# analog-out.net
KiCad netlist of a schematic drawn in EAGLE
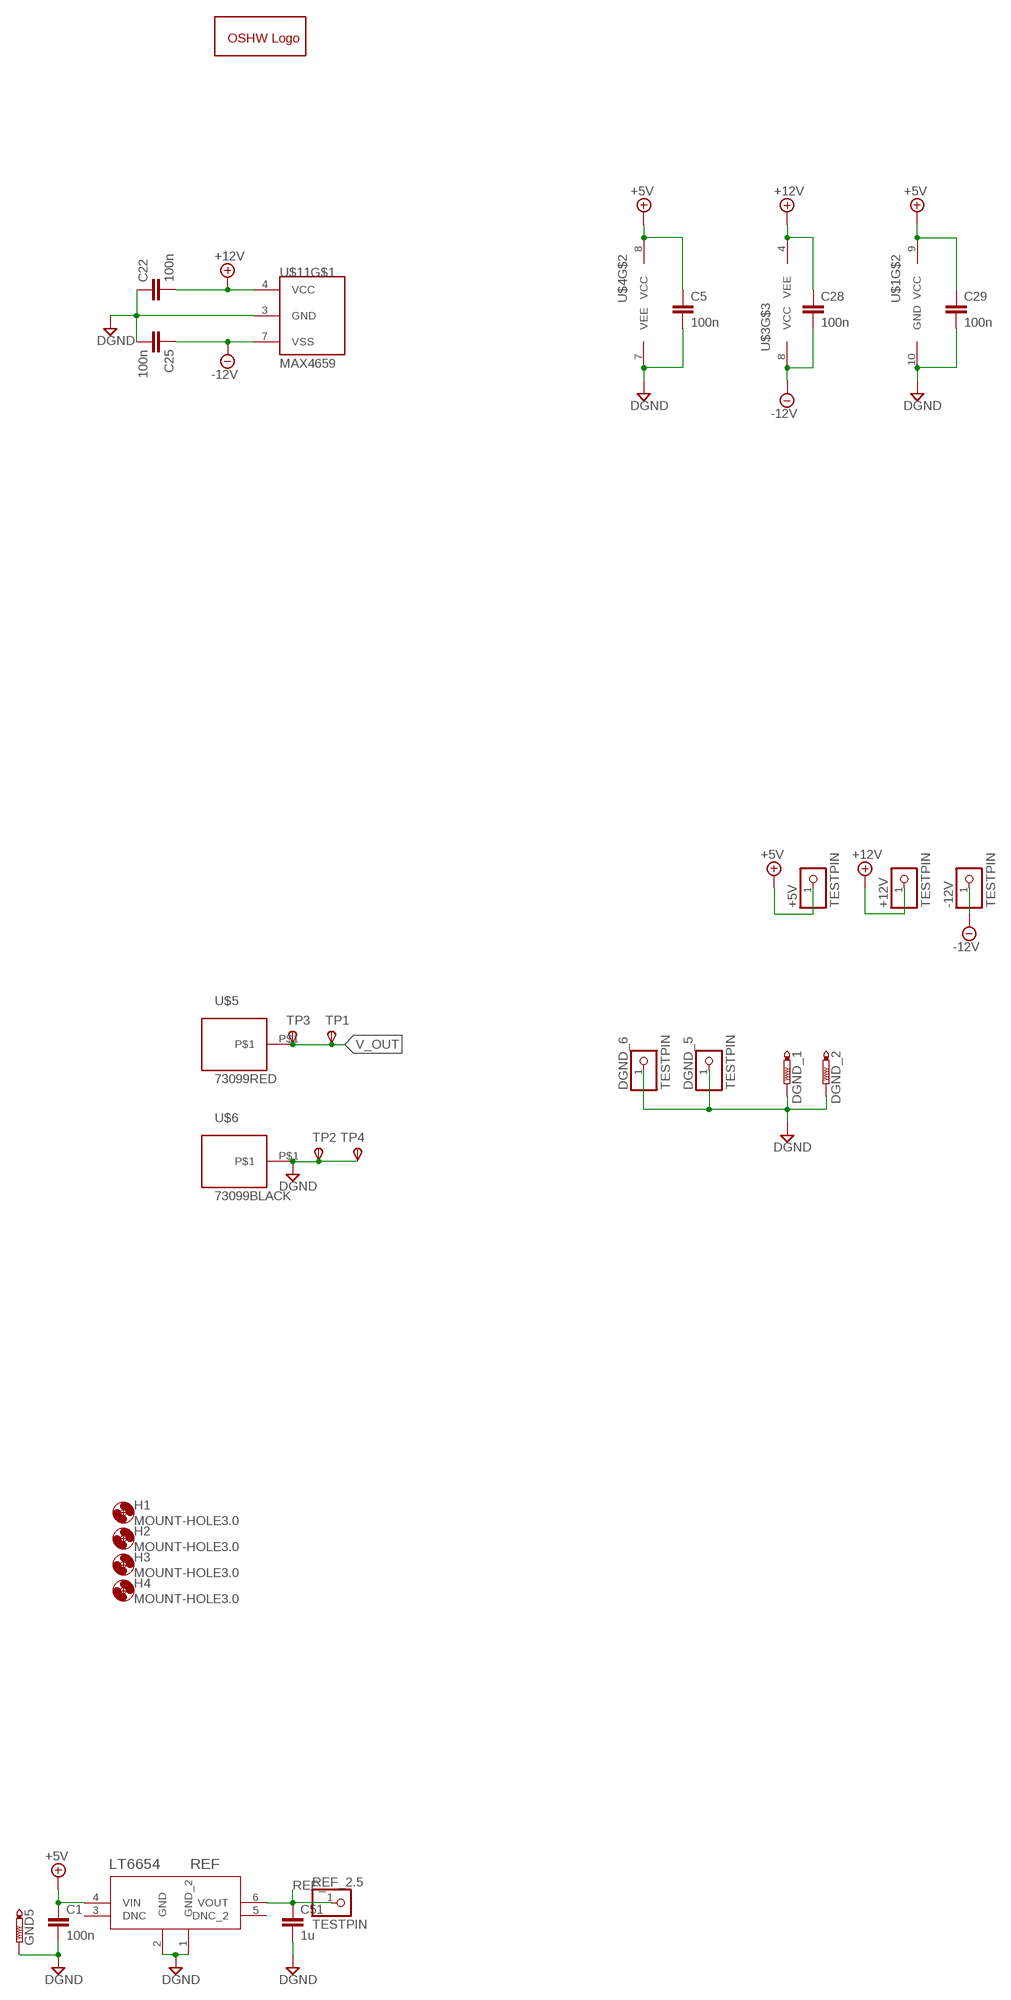
[diagram p0: schematic, sheet 1, part 1 of 2]
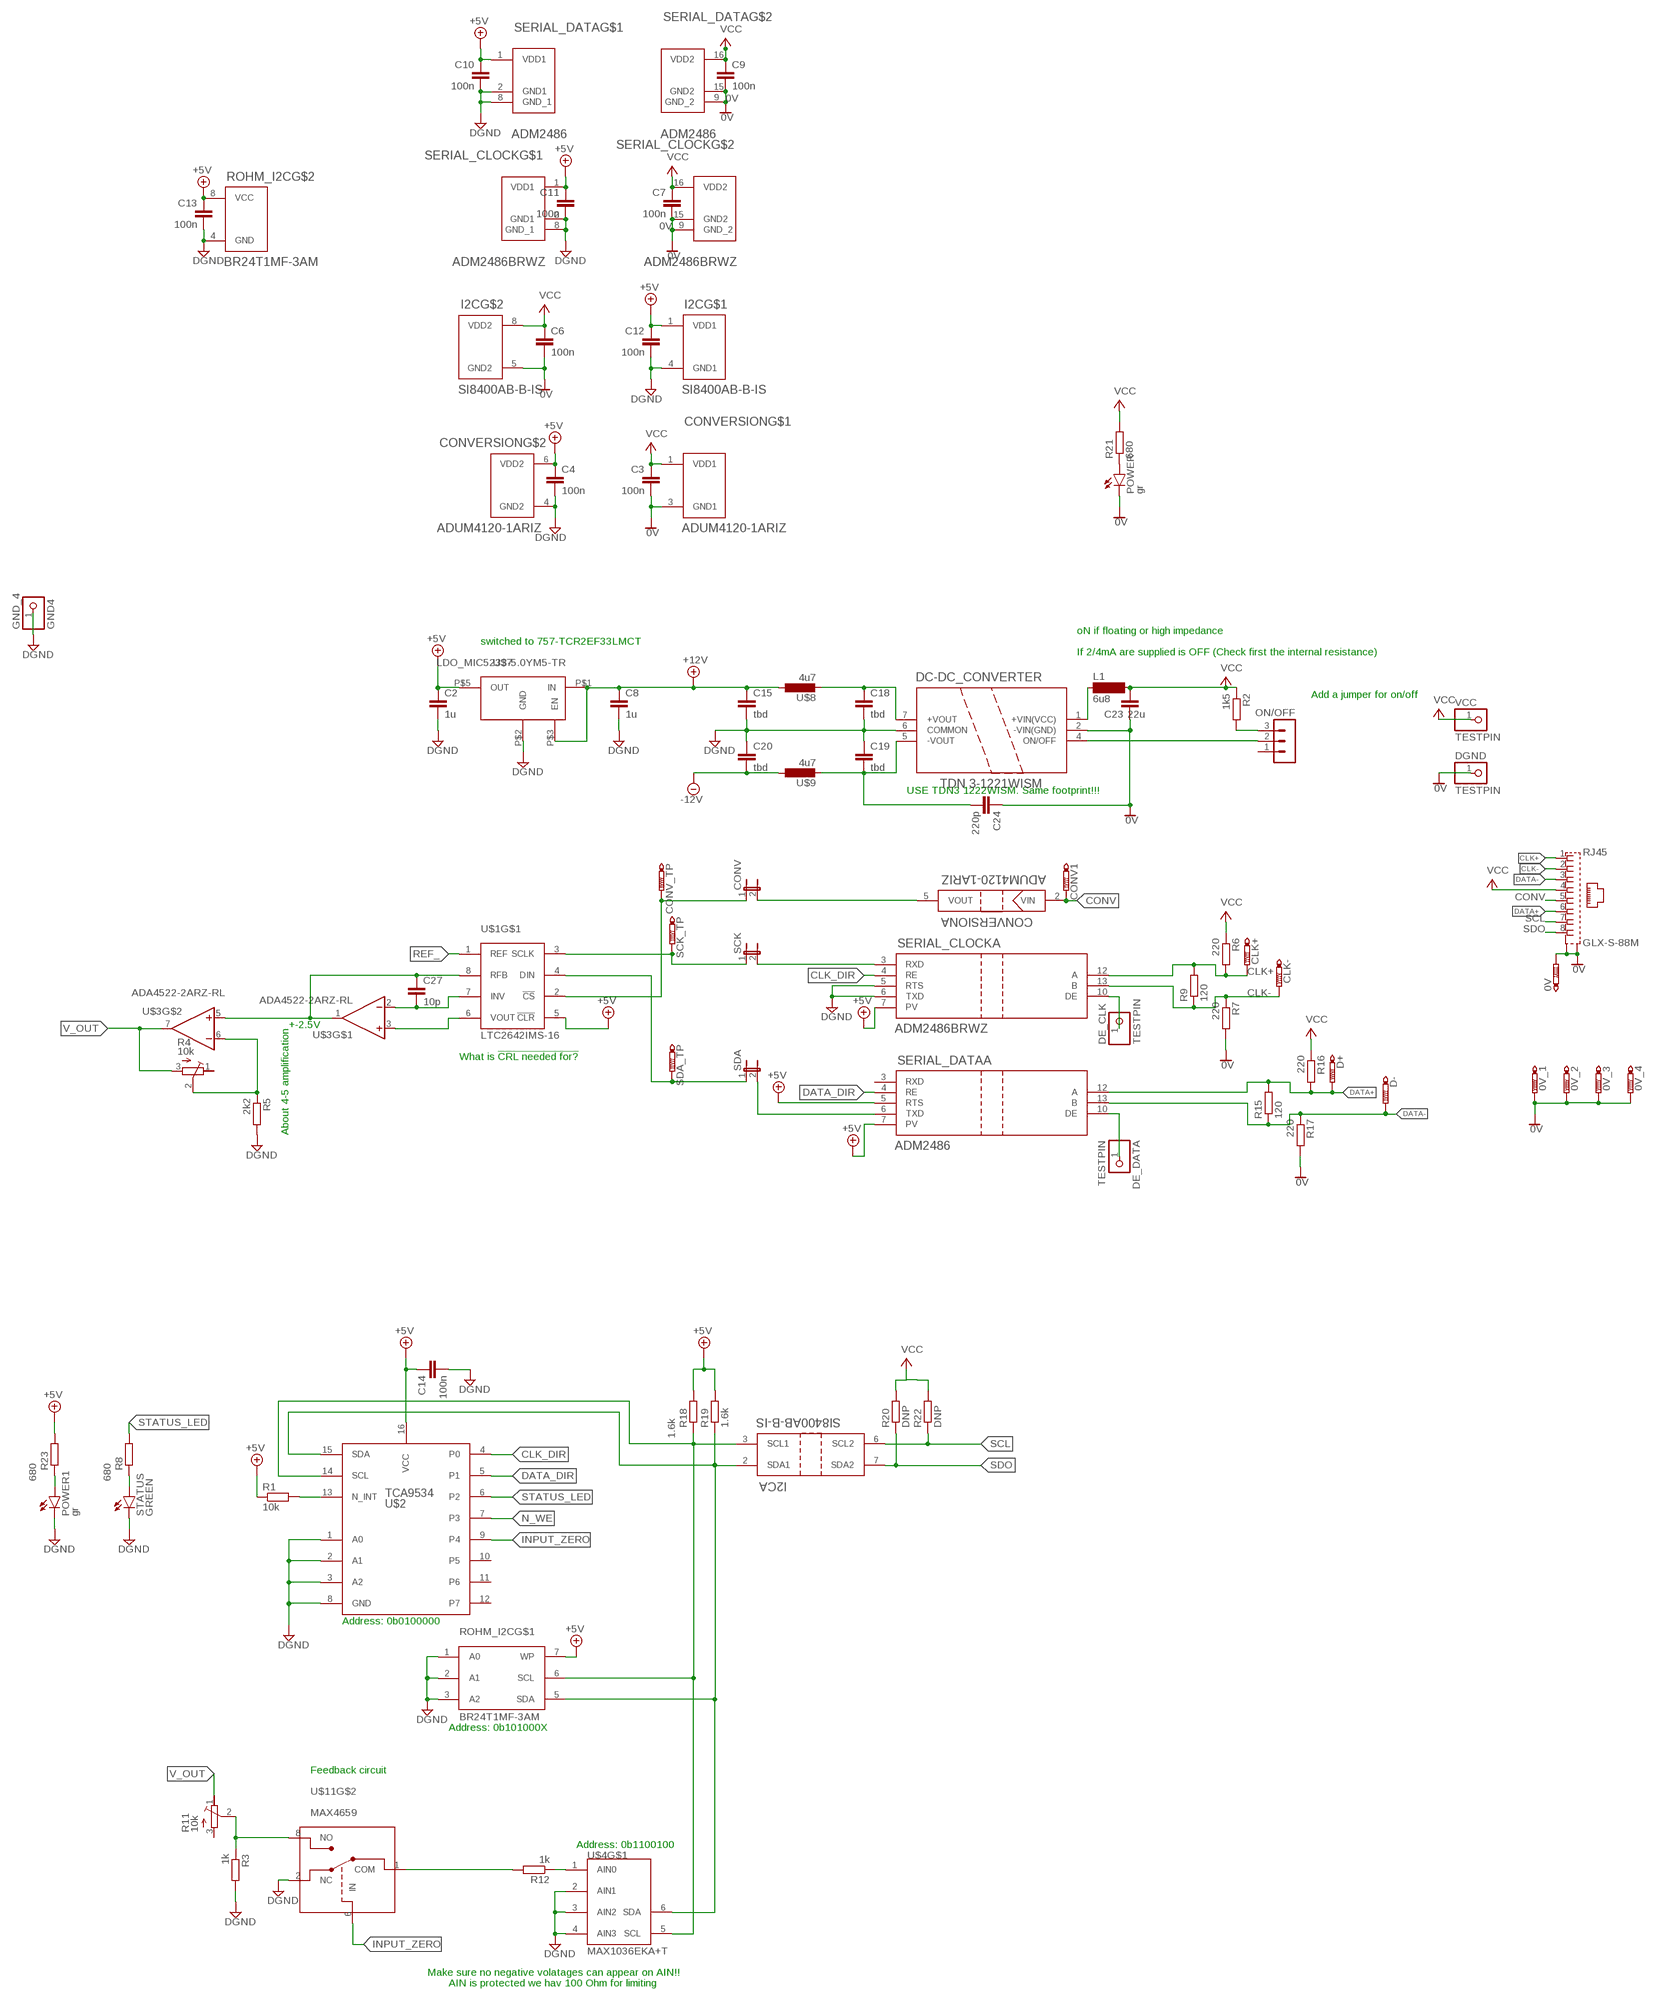
[diagram p1: schematic, sheet 1, part 2 of 2]

(export (version "E")
  (design (tool "Eeschema 10.0.6"))
  (components
    (comp (ref "+5V")
      (value "TESTPIN")
      (footprint "eagle-import:1X01")
      (libsource (lib "eagle-import") (part "TESTPIN"))
    )
    (comp (ref "+12V")
      (value "TESTPIN")
      (footprint "eagle-import:1X01")
      (libsource (lib "eagle-import") (part "TESTPIN"))
    )
    (comp (ref "-12V")
      (value "TESTPIN")
      (footprint "eagle-import:1X01")
      (libsource (lib "eagle-import") (part "TESTPIN"))
    )
    (comp (ref "0V")
      (value "PTR1B1,27")
      (footprint "eagle-import:B1,27")
      (libsource (lib "eagle-import") (part "PTR1B1,27"))
    )
    (comp (ref "0V_1")
      (value "PTR1B1,27")
      (footprint "eagle-import:B1,27")
      (libsource (lib "eagle-import") (part "PTR1B1,27"))
    )
    (comp (ref "0V_2")
      (value "PTR1B1,27")
      (footprint "eagle-import:B1,27")
      (libsource (lib "eagle-import") (part "PTR1B1,27"))
    )
    (comp (ref "0V_3")
      (value "PTR1B1,27")
      (footprint "eagle-import:B1,27")
      (libsource (lib "eagle-import") (part "PTR1B1,27"))
    )
    (comp (ref "0V_4")
      (value "PTR1B1,27")
      (footprint "eagle-import:B1,27")
      (libsource (lib "eagle-import") (part "PTR1B1,27"))
    )
    (comp (ref "C1")
      (value "100n")
      (footprint "eagle-import:C0805")
      (libsource (lib "eagle-import") (part "C-EUC0805"))
    )
    (comp (ref "C2")
      (value "1u")
      (footprint "eagle-import:C0805K")
      (libsource (lib "eagle-import") (part "C-EUC0805K"))
    )
    (comp (ref "C3")
      (value "100n")
      (footprint "eagle-import:C0805K")
      (libsource (lib "eagle-import") (part "C-EUC0805K"))
    )
    (comp (ref "C4")
      (value "100n")
      (footprint "eagle-import:C0805K")
      (libsource (lib "eagle-import") (part "C-EUC0805K"))
    )
    (comp (ref "C5")
      (value "100n")
      (footprint "eagle-import:C0805")
      (libsource (lib "eagle-import") (part "C-EUC0805"))
    )
    (comp (ref "C6")
      (value "100n")
      (footprint "eagle-import:C0805K")
      (libsource (lib "eagle-import") (part "C-EUC0805K"))
    )
    (comp (ref "C7")
      (value "100n")
      (footprint "eagle-import:C0805K")
      (libsource (lib "eagle-import") (part "C-EUC0805K"))
    )
    (comp (ref "C8")
      (value "1u")
      (footprint "eagle-import:C0805K")
      (libsource (lib "eagle-import") (part "C-EUC0805K"))
    )
    (comp (ref "C9")
      (value "100n")
      (footprint "eagle-import:C0805K")
      (libsource (lib "eagle-import") (part "C-EUC0805K"))
    )
    (comp (ref "C10")
      (value "100n")
      (footprint "eagle-import:C0805K")
      (libsource (lib "eagle-import") (part "C-EUC0805K"))
    )
    (comp (ref "C11")
      (value "100n")
      (footprint "eagle-import:C0805K")
      (libsource (lib "eagle-import") (part "C-EUC0805K"))
    )
    (comp (ref "C12")
      (value "100n")
      (footprint "eagle-import:C0805K")
      (libsource (lib "eagle-import") (part "C-EUC0805K"))
    )
    (comp (ref "C13")
      (value "100n")
      (footprint "eagle-import:C0805K")
      (libsource (lib "eagle-import") (part "C-EUC0805K"))
    )
    (comp (ref "C14")
      (value "100n")
      (footprint "eagle-import:C0805K")
      (libsource (lib "eagle-import") (part "C-EUC0805K"))
    )
    (comp (ref "C15")
      (value "tbd")
      (footprint "eagle-import:C0805K")
      (libsource (lib "eagle-import") (part "C-EUC0805K"))
    )
    (comp (ref "C18")
      (value "tbd")
      (footprint "eagle-import:C0805K")
      (libsource (lib "eagle-import") (part "C-EUC0805K"))
    )
    (comp (ref "C19")
      (value "tbd")
      (footprint "eagle-import:C0805K")
      (libsource (lib "eagle-import") (part "C-EUC0805K"))
    )
    (comp (ref "C20")
      (value "tbd")
      (footprint "eagle-import:C0805K")
      (libsource (lib "eagle-import") (part "C-EUC0805K"))
    )
    (comp (ref "C22")
      (value "100n")
      (footprint "eagle-import:C0805")
      (libsource (lib "eagle-import") (part "C-EUC0805"))
    )
    (comp (ref "C23")
      (value "22u")
      (footprint "eagle-import:C1206")
      (libsource (lib "eagle-import") (part "C-EUC1206"))
    )
    (comp (ref "C24")
      (value "220p")
      (footprint "eagle-import:C1808")
      (libsource (lib "eagle-import") (part "C-EUC1808"))
    )
    (comp (ref "C25")
      (value "100n")
      (footprint "eagle-import:C0805")
      (libsource (lib "eagle-import") (part "C-EUC0805"))
    )
    (comp (ref "C27")
      (value "10p")
      (footprint "eagle-import:C0805")
      (libsource (lib "eagle-import") (part "C-EUC0805"))
    )
    (comp (ref "C28")
      (value "100n")
      (footprint "eagle-import:C0805")
      (libsource (lib "eagle-import") (part "C-EUC0805"))
    )
    (comp (ref "C29")
      (value "100n")
      (footprint "eagle-import:C0805")
      (libsource (lib "eagle-import") (part "C-EUC0805"))
    )
    (comp (ref "C51")
      (value "1u")
      (footprint "eagle-import:C0805")
      (libsource (lib "eagle-import") (part "C-EUC0805"))
    )
    (comp (ref "CLK+")
      (value "PTR1B1,27")
      (footprint "eagle-import:B1,27")
      (libsource (lib "eagle-import") (part "PTR1B1,27"))
    )
    (comp (ref "CLK-")
      (value "PTR1B1,27")
      (footprint "eagle-import:B1,27")
      (libsource (lib "eagle-import") (part "PTR1B1,27"))
    )
    (comp (ref "CONV")
      (value "JP1E")
      (footprint "eagle-import:JP1")
      (libsource (lib "eagle-import") (part "JP1E"))
    )
    (comp (ref "CONV1")
      (value "PTR1B1,27")
      (footprint "eagle-import:B1,27")
      (libsource (lib "eagle-import") (part "PTR1B1,27"))
    )
    (comp (ref "CONVERSION")
      (value "ADUM4120-1ARIZ")
      (footprint "eagle-import:RI_6_1_ADI")
      (fields (field (name "DIGIKEY") "ADUM4120-1ARIZ-ND"))
      (libsource (lib "eagle-import") (part "ADUM4120-1ARIZ"))
    )
    (comp (ref "CONV_TP")
      (value "PTR1B1,27")
      (footprint "eagle-import:B1,27")
      (libsource (lib "eagle-import") (part "PTR1B1,27"))
    )
    (comp (ref "D+")
      (value "PTR1B1,27")
      (footprint "eagle-import:B1,27")
      (libsource (lib "eagle-import") (part "PTR1B1,27"))
    )
    (comp (ref "D-")
      (value "PTR1B1,27")
      (footprint "eagle-import:B1,27")
      (libsource (lib "eagle-import") (part "PTR1B1,27"))
    )
    (comp (ref "DC-DC_CONVERTER")
      (value "TDN 3-1221WISM")
      (footprint "eagle-import:TDN3_TRP")
      (fields
        (field (name "MANUFACTURER_PART_NUMBER") "TDN 3-1211WI")
        (field (name "COPYRIGHT") "Copyright (C) 2018 Accelerated Designs. All rights reserved")
      )
      (libsource (lib "eagle-import") (part "TDN_3-1211WI"))
    )
    (comp (ref "DE_CLK")
      (value "TESTPIN")
      (footprint "eagle-import:1X01")
      (libsource (lib "eagle-import") (part "TESTPIN"))
    )
    (comp (ref "DE_DATA")
      (value "TESTPIN")
      (footprint "eagle-import:1X01")
      (libsource (lib "eagle-import") (part "TESTPIN"))
    )
    (comp (ref "DGND")
      (value "TESTPIN")
      (footprint "eagle-import:1X01")
      (libsource (lib "eagle-import") (part "TESTPIN"))
    )
    (comp (ref "DGND_1")
      (value "PTR1B1,27")
      (footprint "eagle-import:B1,27")
      (libsource (lib "eagle-import") (part "PTR1B1,27"))
    )
    (comp (ref "DGND_2")
      (value "PTR1B1,27")
      (footprint "eagle-import:B1,27")
      (libsource (lib "eagle-import") (part "PTR1B1,27"))
    )
    (comp (ref "DGND_5")
      (value "TESTPIN")
      (footprint "eagle-import:1X01")
      (libsource (lib "eagle-import") (part "TESTPIN"))
    )
    (comp (ref "DGND_6")
      (value "TESTPIN")
      (footprint "eagle-import:1X01")
      (libsource (lib "eagle-import") (part "TESTPIN"))
    )
    (comp (ref "GND5")
      (value "PTR1B1,27")
      (footprint "eagle-import:B1,27")
      (libsource (lib "eagle-import") (part "PTR1B1,27"))
    )
    (comp (ref "GND_4")
      (value "GND4")
      (footprint "eagle-import:1X01")
      (libsource (lib "eagle-import") (part "TESTPIN"))
    )
    (comp (ref "GOLD_ORB_SM1")
      (value "OSHWLOGOLOGO8MM")
      (footprint "eagle-import:OSHW_8MM")
      (libsource (lib "eagle-import") (part "OSHWLOGOLOGO8MM"))
    )
    (comp (ref "H1")
      (value "MOUNT-HOLE3.0")
      (footprint "eagle-import:3,0")
      (libsource (lib "eagle-import") (part "MOUNT-HOLE3.0"))
    )
    (comp (ref "H2")
      (value "MOUNT-HOLE3.0")
      (footprint "eagle-import:3,0")
      (libsource (lib "eagle-import") (part "MOUNT-HOLE3.0"))
    )
    (comp (ref "H3")
      (value "MOUNT-HOLE3.0")
      (footprint "eagle-import:3,0")
      (libsource (lib "eagle-import") (part "MOUNT-HOLE3.0"))
    )
    (comp (ref "H4")
      (value "MOUNT-HOLE3.0")
      (footprint "eagle-import:3,0")
      (libsource (lib "eagle-import") (part "MOUNT-HOLE3.0"))
    )
    (comp (ref "I2C")
      (value "SI8400AB-B-IS")
      (footprint "eagle-import:R_8_ADI")
      (fields
        (field (name "MANUFACTURER_PART_NUMBER") "ADUM1251WARZ")
        (field (name "DIGIKEY") "ADUM1251ARZ-RL7TR-ND")
        (field (name "COPYRIGHT") "Copyright (C) 2018 Accelerated Designs. All rights reserved")
      )
      (libsource (lib "eagle-import") (part "ADUM1251WARZ"))
    )
    (comp (ref "L1")
      (value "6u8")
      (footprint "eagle-import:SM-NE29")
      (libsource (lib "eagle-import") (part "SM-NE29"))
    )
    (comp (ref "ON/OFF")
      (value "MA03-1")
      (footprint "eagle-import:MA03-1")
      (libsource (lib "eagle-import") (part "MA03-1"))
    )
    (comp (ref "POWER")
      (value "gr")
      (footprint "eagle-import:SML0805")
      (libsource (lib "eagle-import") (part "LEDSML0805"))
    )
    (comp (ref "POWER1")
      (value "gr")
      (footprint "eagle-import:SML0805")
      (libsource (lib "eagle-import") (part "LEDSML0805"))
    )
    (comp (ref "R1")
      (value "10k")
      (footprint "eagle-import:R0805")
      (libsource (lib "eagle-import") (part "R-EU_R0805"))
    )
    (comp (ref "R2")
      (value "1k5")
      (footprint "eagle-import:R0805")
      (libsource (lib "eagle-import") (part "R-EU_R0805"))
    )
    (comp (ref "R3")
      (value "1k")
      (footprint "eagle-import:R0805")
      (libsource (lib "eagle-import") (part "R-EU_R0805"))
    )
    (comp (ref "R4")
      (value "10k")
      (footprint "eagle-import:RTRIMT93YA")
      (libsource (lib "eagle-import") (part "R-TRIMMT93YA"))
    )
    (comp (ref "R5")
      (value "2k2")
      (footprint "eagle-import:R0805")
      (libsource (lib "eagle-import") (part "R-EU_R0805"))
    )
    (comp (ref "R6")
      (value "220")
      (footprint "eagle-import:R0805")
      (libsource (lib "eagle-import") (part "R-EU_R0805"))
    )
    (comp (ref "R7")
      (value "220")
      (footprint "eagle-import:R0805")
      (libsource (lib "eagle-import") (part "R-EU_R0805"))
    )
    (comp (ref "R8")
      (value "680")
      (footprint "eagle-import:R0805")
      (libsource (lib "eagle-import") (part "resistor_348_R-EU_R0805"))
    )
    (comp (ref "R9")
      (value "120")
      (footprint "eagle-import:R0805")
      (libsource (lib "eagle-import") (part "R-EU_R0805"))
    )
    (comp (ref "R11")
      (value "10k")
      (footprint "eagle-import:RTRIMT93YA")
      (libsource (lib "eagle-import") (part "R-TRIMMT93YA"))
    )
    (comp (ref "R12")
      (value "1k")
      (footprint "eagle-import:R0805")
      (libsource (lib "eagle-import") (part "resistor_348_R-EU_R0805"))
    )
    (comp (ref "R15")
      (value "120")
      (footprint "eagle-import:R0805")
      (libsource (lib "eagle-import") (part "R-EU_R0805"))
    )
    (comp (ref "R16")
      (value "220")
      (footprint "eagle-import:R0805")
      (libsource (lib "eagle-import") (part "R-EU_R0805"))
    )
    (comp (ref "R17")
      (value "220")
      (footprint "eagle-import:R0805")
      (libsource (lib "eagle-import") (part "R-EU_R0805"))
    )
    (comp (ref "R18")
      (value "1.6k")
      (footprint "eagle-import:R0805")
      (libsource (lib "eagle-import") (part "resistor_348_R-EU_R0805"))
    )
    (comp (ref "R19")
      (value "1.6k")
      (footprint "eagle-import:R0805")
      (libsource (lib "eagle-import") (part "resistor_348_R-EU_R0805"))
    )
    (comp (ref "R20")
      (value "DNP")
      (footprint "eagle-import:R0805")
      (libsource (lib "eagle-import") (part "resistor_348_R-EU_R0805"))
    )
    (comp (ref "R21")
      (value "680")
      (footprint "eagle-import:R0805")
      (libsource (lib "eagle-import") (part "R-EU_R0805"))
    )
    (comp (ref "R22")
      (value "DNP")
      (footprint "eagle-import:R0805")
      (libsource (lib "eagle-import") (part "resistor_348_R-EU_R0805"))
    )
    (comp (ref "R23")
      (value "680")
      (footprint "eagle-import:R0805")
      (libsource (lib "eagle-import") (part "resistor_348_R-EU_R0805"))
    )
    (comp (ref "REF")
      (value "LT6654")
      (footprint "eagle-import:S_6_ADI")
      (fields
        (field (name "MANUFACTURER_PART_NUMBER") "LT6654AIS6-2.048#TRMPBF")
        (field (name "COPYRIGHT") "Copyright (C) 2016 Accelerated Designs. All rights reserved")
      )
      (libsource (lib "eagle-import") (part "LT6654AIS6-2.048TRMPBF"))
    )
    (comp (ref "REF_2.5")
      (value "TESTPIN")
      (footprint "eagle-import:1X01")
      (libsource (lib "eagle-import") (part "TESTPIN"))
    )
    (comp (ref "RJ45")
      (value "GLX-S-88M")
      (footprint "eagle-import:GLX-S-88M")
      (libsource (lib "eagle-import") (part "GLX-S-88M"))
    )
    (comp (ref "ROHM_I2C")
      (value "BR24T1MF-3AM")
      (footprint "eagle-import:BR24T1MFJ-3AM")
      (fields (field (name "DIGIKEY") "BR24T1MF-3AME2TR-ND"))
      (libsource (lib "eagle-import") (part "BR24T1MF-3AM"))
    )
    (comp (ref "SCK")
      (value "JP1E")
      (footprint "eagle-import:JP1")
      (libsource (lib "eagle-import") (part "JP1E"))
    )
    (comp (ref "SCK_TP")
      (value "PTR1B1,27")
      (footprint "eagle-import:B1,27")
      (libsource (lib "eagle-import") (part "PTR1B1,27"))
    )
    (comp (ref "SDA")
      (value "JP1E")
      (footprint "eagle-import:JP1")
      (libsource (lib "eagle-import") (part "JP1E"))
    )
    (comp (ref "SDA_TP")
      (value "PTR1B1,27")
      (footprint "eagle-import:B1,27")
      (libsource (lib "eagle-import") (part "PTR1B1,27"))
    )
    (comp (ref "SERIAL_CLOCK")
      (value "ADM2486BRWZ")
      (footprint "eagle-import:RW_16_ADI")
      (fields
        (field (name "MANUFACTURER_PART_NUMBER") "ADM2486BRWZ-REEL")
        (field (name "DIGIKEY") "ADM2486BRWZ-REELTR-ND")
      )
      (libsource (lib "eagle-import") (part "ADM2486BRWZ-REEL"))
    )
    (comp (ref "SERIAL_DATA")
      (value "ADM2486")
      (footprint "eagle-import:RW_16_ADI")
      (fields
        (field (name "MANUFACTURER_PART_NUMBER") "ADM2486BRWZ-REEL")
        (field (name "DIGIKEY") "ADM2486BRWZ-REELTR-ND")
      )
      (libsource (lib "eagle-import") (part "ADM2486BRWZ-REEL"))
    )
    (comp (ref "STATUS")
      (value "GREEN")
      (footprint "eagle-import:CHIPLED_0805")
      (libsource (lib "eagle-import") (part "LEDCHIPLED_0805"))
    )
    (comp (ref "TP1")
      (value "TPSTP20SQ")
      (footprint "eagle-import:TP20SQ")
      (libsource (lib "eagle-import") (part "TPSTP20SQ"))
    )
    (comp (ref "TP2")
      (value "TPSTP20SQ")
      (footprint "eagle-import:TP20SQ")
      (libsource (lib "eagle-import") (part "TPSTP20SQ"))
    )
    (comp (ref "TP3")
      (value "TPSTP20SQ")
      (footprint "eagle-import:TP20SQ")
      (libsource (lib "eagle-import") (part "TPSTP20SQ"))
    )
    (comp (ref "TP4")
      (value "TPSTP20SQ")
      (footprint "eagle-import:TP20SQ")
      (libsource (lib "eagle-import") (part "TPSTP20SQ"))
    )
    (comp (ref "U$1")
      (value "LTC2642IMS-16")
      (footprint "eagle-import:MSOP10")
      (libsource (lib "eagle-import") (part "LTC2642IMS-16"))
    )
    (comp (ref "U$2")
      (value "TCA9534")
      (footprint "eagle-import:TSSOP16L")
      (libsource (lib "eagle-import") (part "TCA9534"))
    )
    (comp (ref "U$3")
      (value "ADA4522-2ARZ-RL")
      (footprint "eagle-import:MSOP8")
      (libsource (lib "eagle-import") (part "ADA4522-2ARZ-RL"))
    )
    (comp (ref "U$4")
      (value "MAX1036EKA+T")
      (footprint "eagle-import:SOT23-8L")
      (libsource (lib "eagle-import") (part "MAX1036EKA+T"))
    )
    (comp (ref "U$5")
      (value "73099RED")
      (footprint "eagle-import:4MM_BANANA")
      (libsource (lib "eagle-import") (part "73099RED"))
    )
    (comp (ref "U$6")
      (value "73099BLACK")
      (footprint "eagle-import:4MM_BANANA")
      (libsource (lib "eagle-import") (part "73099BLACK"))
    )
    (comp (ref "U$7")
      (value "LDO_MIC5233-5.0YM5-TR")
      (footprint "eagle-import:SOT23-5")
      (libsource (lib "eagle-import") (part "LDO_MIC5233-5.0YM5-TR"))
    )
    (comp (ref "U$8")
      (value "4u7")
      (footprint "eagle-import:L5038P")
      (libsource (lib "eagle-import") (part "NRS5010T4R7MMGF"))
    )
    (comp (ref "U$9")
      (value "4u7")
      (footprint "eagle-import:L5038P")
      (libsource (lib "eagle-import") (part "NRS5010T4R7MMGF"))
    )
    (comp (ref "U$11")
      (value "MAX4659")
      (footprint "eagle-import:UMAX8")
      (fields (field (name "MOUSER") "700-MAX4659EUA"))
      (libsource (lib "eagle-import") (part "MAX4659"))
    )
    (comp (ref "VCC")
      (value "TESTPIN")
      (footprint "eagle-import:1X01")
      (libsource (lib "eagle-import") (part "TESTPIN"))
    )
  )
  (nets
    (net (code "1") (name "+5V") (class "Default")
      (node (ref "+5V") (pin "1") (pinfunction "1_1") (pintype "passive"))
      (node (ref "C1") (pin "1") (pinfunction "1_1") (pintype "passive"))
      (node (ref "C10") (pin "1") (pinfunction "1_1") (pintype "passive"))
      (node (ref "C11") (pin "1") (pinfunction "1_1") (pintype "passive"))
      (node (ref "C12") (pin "1") (pinfunction "1_1") (pintype "passive"))
      (node (ref "C13") (pin "1") (pinfunction "1_1") (pintype "passive"))
      (node (ref "C14") (pin "1") (pinfunction "1_1") (pintype "passive"))
      (node (ref "C2") (pin "1") (pinfunction "1_1") (pintype "passive"))
      (node (ref "C29") (pin "1") (pinfunction "1_1") (pintype "passive"))
      (node (ref "C4") (pin "1") (pinfunction "1_1") (pintype "passive"))
      (node (ref "C5") (pin "1") (pinfunction "1_1") (pintype "passive"))
      (node (ref "CONVERSION") (pin "6") (pinfunction "VDD2_6") (pintype "passive"))
      (node (ref "I2C") (pin "1") (pinfunction "VDD1_1") (pintype "power_in"))
      (node (ref "R1") (pin "1") (pinfunction "1_1") (pintype "passive"))
      (node (ref "R18") (pin "2") (pinfunction "2_2") (pintype "passive"))
      (node (ref "R19") (pin "2") (pinfunction "2_2") (pintype "passive"))
      (node (ref "R23") (pin "2") (pinfunction "2_2") (pintype "passive"))
      (node (ref "REF") (pin "4") (pinfunction "VIN_4") (pintype "input"))
      (node (ref "ROHM_I2C") (pin "7") (pinfunction "WP_7") (pintype "input"))
      (node (ref "ROHM_I2C") (pin "8") (pinfunction "VCC_8") (pintype "passive"))
      (node (ref "SERIAL_CLOCK") (pin "1") (pinfunction "VDD1_1") (pintype "power_in"))
      (node (ref "SERIAL_CLOCK") (pin "7") (pinfunction "PV_7") (pintype "passive"))
      (node (ref "SERIAL_DATA") (pin "1") (pinfunction "VDD1_1") (pintype "power_in"))
      (node (ref "SERIAL_DATA") (pin "5") (pinfunction "RTS_5") (pintype "passive"))
      (node (ref "SERIAL_DATA") (pin "7") (pinfunction "PV_7") (pintype "passive"))
      (node (ref "U$1") (pin "5") (pinfunction "~{CLR}_5") (pintype "bidirectional"))
      (node (ref "U$1") (pin "9") (pinfunction "VCC_9") (pintype "bidirectional"))
      (node (ref "U$2") (pin "16") (pinfunction "VCC_16") (pintype "bidirectional"))
      (node (ref "U$4") (pin "8") (pinfunction "VCC_8") (pintype "bidirectional"))
      (node (ref "U$7") (pin "P$5") (pinfunction "OUT_P$5") (pintype "bidirectional"))
    )
    (net (code "2") (name "+12V") (class "Default")
      (node (ref "+12V") (pin "1") (pinfunction "1_1") (pintype "passive"))
      (node (ref "C15") (pin "1") (pinfunction "1_1") (pintype "passive"))
      (node (ref "C22") (pin "2") (pinfunction "2_2") (pintype "passive"))
      (node (ref "C28") (pin "1") (pinfunction "1_1") (pintype "passive"))
      (node (ref "C8") (pin "1") (pinfunction "1_1") (pintype "passive"))
      (node (ref "U$11") (pin "4") (pinfunction "VCC_4") (pintype "bidirectional"))
      (node (ref "U$3") (pin "4") (pinfunction "VEE_4") (pintype "bidirectional"))
      (node (ref "U$7") (pin "P$1") (pinfunction "IN_P$1") (pintype "bidirectional"))
      (node (ref "U$7") (pin "P$3") (pinfunction "EN_P$3") (pintype "bidirectional"))
      (node (ref "U$8") (pin "1") (pinfunction "1_1") (pintype "passive"))
    )
    (net (code "3") (name "-12V") (class "Default")
      (node (ref "-12V") (pin "1") (pinfunction "1_1") (pintype "passive"))
      (node (ref "C20") (pin "2") (pinfunction "2_2") (pintype "passive"))
      (node (ref "C25") (pin "1") (pinfunction "1_1") (pintype "passive"))
      (node (ref "C28") (pin "2") (pinfunction "2_2") (pintype "passive"))
      (node (ref "U$11") (pin "7") (pinfunction "VSS_7") (pintype "bidirectional"))
      (node (ref "U$3") (pin "8") (pinfunction "VCC_8") (pintype "bidirectional"))
      (node (ref "U$9") (pin "1") (pinfunction "1_1") (pintype "passive"))
    )
    (net (code "4") (name "0V") (class "Default")
      (node (ref "0V") (pin "TP") (pinfunction "TP_TP") (pintype "input"))
      (node (ref "0V_1") (pin "TP") (pinfunction "TP_TP") (pintype "input"))
      (node (ref "0V_2") (pin "TP") (pinfunction "TP_TP") (pintype "input"))
      (node (ref "0V_3") (pin "TP") (pinfunction "TP_TP") (pintype "input"))
      (node (ref "0V_4") (pin "TP") (pinfunction "TP_TP") (pintype "input"))
      (node (ref "C23") (pin "1") (pinfunction "1_1") (pintype "passive"))
      (node (ref "C24") (pin "1") (pinfunction "1_1") (pintype "passive"))
      (node (ref "C3") (pin "2") (pinfunction "2_2") (pintype "passive"))
      (node (ref "C6") (pin "2") (pinfunction "2_2") (pintype "passive"))
      (node (ref "C7") (pin "2") (pinfunction "2_2") (pintype "passive"))
      (node (ref "C9") (pin "2") (pinfunction "2_2") (pintype "passive"))
      (node (ref "CONVERSION") (pin "3") (pinfunction "GND1_3") (pintype "passive"))
      (node (ref "DC-DC_CONVERTER") (pin "2") (pinfunction "-VIN(GND)_2") (pintype "passive"))
      (node (ref "DGND") (pin "1") (pinfunction "1_1") (pintype "passive"))
      (node (ref "I2C") (pin "5") (pinfunction "GND2_5") (pintype "passive"))
      (node (ref "POWER") (pin "C") (pinfunction "C_C") (pintype "passive"))
      (node (ref "R17") (pin "2") (pinfunction "2_2") (pintype "passive"))
      (node (ref "R7") (pin "2") (pinfunction "2_2") (pintype "passive"))
      (node (ref "RJ45") (pin "S1") (pinfunction "S1_S1") (pintype "passive"))
      (node (ref "RJ45") (pin "S2") (pinfunction "S2_S2") (pintype "passive"))
      (node (ref "SERIAL_CLOCK") (pin "15") (pinfunction "GND2_15") (pintype "power_in"))
      (node (ref "SERIAL_CLOCK") (pin "9") (pinfunction "GND_2_9") (pintype "power_in"))
      (node (ref "SERIAL_DATA") (pin "15") (pinfunction "GND2_15") (pintype "power_in"))
      (node (ref "SERIAL_DATA") (pin "9") (pinfunction "GND_2_9") (pintype "power_in"))
    )
    (net (code "5") (name "CLK+") (class "Default")
      (node (ref "CLK+") (pin "TP") (pinfunction "TP_TP") (pintype "input"))
      (node (ref "R6") (pin "2") (pinfunction "2_2") (pintype "passive"))
      (node (ref "R9") (pin "2") (pinfunction "2_2") (pintype "passive"))
      (node (ref "RJ45") (pin "1") (pinfunction "1_1") (pintype "passive"))
      (node (ref "SERIAL_CLOCK") (pin "12") (pinfunction "A_12") (pintype "passive"))
    )
    (net (code "6") (name "CLK-") (class "Default")
      (node (ref "CLK-") (pin "TP") (pinfunction "TP_TP") (pintype "input"))
      (node (ref "R7") (pin "1") (pinfunction "1_1") (pintype "passive"))
      (node (ref "R9") (pin "1") (pinfunction "1_1") (pintype "passive"))
      (node (ref "RJ45") (pin "2") (pinfunction "2_2") (pintype "passive"))
      (node (ref "SERIAL_CLOCK") (pin "13") (pinfunction "B_13") (pintype "passive"))
    )
    (net (code "7") (name "CLK_DIR") (class "Default")
      (node (ref "SERIAL_CLOCK") (pin "4") (pinfunction "RE_4") (pintype "passive"))
      (node (ref "U$2") (pin "4") (pinfunction "P0_4") (pintype "bidirectional"))
    )
    (net (code "8") (name "CONV") (class "Default")
      (node (ref "CONV1") (pin "TP") (pinfunction "TP_TP") (pintype "input"))
      (node (ref "CONVERSION") (pin "2") (pinfunction "VIN_2") (pintype "input"))
      (node (ref "RJ45") (pin "5") (pinfunction "5_5") (pintype "passive"))
    )
    (net (code "9") (name "DATA+") (class "Default")
      (node (ref "D+") (pin "TP") (pinfunction "TP_TP") (pintype "input"))
      (node (ref "R15") (pin "2") (pinfunction "2_2") (pintype "passive"))
      (node (ref "R16") (pin "2") (pinfunction "2_2") (pintype "passive"))
      (node (ref "RJ45") (pin "6") (pinfunction "6_6") (pintype "passive"))
      (node (ref "SERIAL_DATA") (pin "12") (pinfunction "A_12") (pintype "passive"))
    )
    (net (code "10") (name "DATA-") (class "Default")
      (node (ref "D-") (pin "TP") (pinfunction "TP_TP") (pintype "input"))
      (node (ref "R15") (pin "1") (pinfunction "1_1") (pintype "passive"))
      (node (ref "R17") (pin "1") (pinfunction "1_1") (pintype "passive"))
      (node (ref "RJ45") (pin "3") (pinfunction "3_3") (pintype "passive"))
      (node (ref "SERIAL_DATA") (pin "13") (pinfunction "B_13") (pintype "passive"))
    )
    (net (code "11") (name "DATA_DIR") (class "Default")
      (node (ref "SERIAL_DATA") (pin "4") (pinfunction "RE_4") (pintype "passive"))
      (node (ref "U$2") (pin "5") (pinfunction "P1_5") (pintype "bidirectional"))
    )
    (net (code "12") (name "DGND") (class "Default")
      (node (ref "C1") (pin "2") (pinfunction "2_2") (pintype "passive"))
      (node (ref "C10") (pin "2") (pinfunction "2_2") (pintype "passive"))
      (node (ref "C11") (pin "2") (pinfunction "2_2") (pintype "passive"))
      (node (ref "C12") (pin "2") (pinfunction "2_2") (pintype "passive"))
      (node (ref "C13") (pin "2") (pinfunction "2_2") (pintype "passive"))
      (node (ref "C14") (pin "2") (pinfunction "2_2") (pintype "passive"))
      (node (ref "C15") (pin "2") (pinfunction "2_2") (pintype "passive"))
      (node (ref "C18") (pin "2") (pinfunction "2_2") (pintype "passive"))
      (node (ref "C19") (pin "1") (pinfunction "1_1") (pintype "passive"))
      (node (ref "C2") (pin "2") (pinfunction "2_2") (pintype "passive"))
      (node (ref "C20") (pin "1") (pinfunction "1_1") (pintype "passive"))
      (node (ref "C22") (pin "1") (pinfunction "1_1") (pintype "passive"))
      (node (ref "C25") (pin "2") (pinfunction "2_2") (pintype "passive"))
      (node (ref "C29") (pin "2") (pinfunction "2_2") (pintype "passive"))
      (node (ref "C4") (pin "2") (pinfunction "2_2") (pintype "passive"))
      (node (ref "C5") (pin "2") (pinfunction "2_2") (pintype "passive"))
      (node (ref "C51") (pin "2") (pinfunction "2_2") (pintype "passive"))
      (node (ref "C8") (pin "2") (pinfunction "2_2") (pintype "passive"))
      (node (ref "CONVERSION") (pin "4") (pinfunction "GND2_4") (pintype "passive"))
      (node (ref "DC-DC_CONVERTER") (pin "6") (pinfunction "COMMON_6") (pintype "output"))
      (node (ref "DGND_1") (pin "TP") (pinfunction "TP_TP") (pintype "input"))
      (node (ref "DGND_2") (pin "TP") (pinfunction "TP_TP") (pintype "input"))
      (node (ref "DGND_5") (pin "1") (pinfunction "1_1") (pintype "passive"))
      (node (ref "DGND_6") (pin "1") (pinfunction "1_1") (pintype "passive"))
      (node (ref "GND5") (pin "TP") (pinfunction "TP_TP") (pintype "input"))
      (node (ref "GND_4") (pin "1") (pinfunction "1_1") (pintype "passive"))
      (node (ref "I2C") (pin "4") (pinfunction "GND1_4") (pintype "power_in"))
      (node (ref "POWER1") (pin "C") (pinfunction "C_C") (pintype "passive"))
      (node (ref "R3") (pin "2") (pinfunction "2_2") (pintype "passive"))
      (node (ref "R5") (pin "2") (pinfunction "2_2") (pintype "passive"))
      (node (ref "REF") (pin "1") (pinfunction "GND_2_1") (pintype "power_in"))
      (node (ref "REF") (pin "2") (pinfunction "GND_2") (pintype "power_in"))
      (node (ref "ROHM_I2C") (pin "1") (pinfunction "A0_1") (pintype "input"))
      (node (ref "ROHM_I2C") (pin "2") (pinfunction "A1_2") (pintype "input"))
      (node (ref "ROHM_I2C") (pin "3") (pinfunction "A2_3") (pintype "input"))
      (node (ref "ROHM_I2C") (pin "4") (pinfunction "GND_4") (pintype "passive"))
      (node (ref "SERIAL_CLOCK") (pin "2") (pinfunction "GND1_2") (pintype "power_in"))
      (node (ref "SERIAL_CLOCK") (pin "5") (pinfunction "RTS_5") (pintype "passive"))
      (node (ref "SERIAL_CLOCK") (pin "6") (pinfunction "TXD_6") (pintype "passive"))
      (node (ref "SERIAL_CLOCK") (pin "8") (pinfunction "GND_1_8") (pintype "power_in"))
      (node (ref "SERIAL_DATA") (pin "2") (pinfunction "GND1_2") (pintype "power_in"))
      (node (ref "SERIAL_DATA") (pin "8") (pinfunction "GND_1_8") (pintype "power_in"))
      (node (ref "STATUS") (pin "C") (pinfunction "C_C") (pintype "passive"))
      (node (ref "TP2") (pin "TP") (pinfunction "PP_TP") (pintype "input"))
      (node (ref "TP4") (pin "TP") (pinfunction "PP_TP") (pintype "input"))
      (node (ref "U$1") (pin "10") (pinfunction "GND_10") (pintype "bidirectional"))
      (node (ref "U$11") (pin "2") (pinfunction "NC_2") (pintype "bidirectional"))
      (node (ref "U$11") (pin "3") (pinfunction "GND_3") (pintype "bidirectional"))
      (node (ref "U$2") (pin "1") (pinfunction "A0_1") (pintype "bidirectional"))
      (node (ref "U$2") (pin "2") (pinfunction "A1_2") (pintype "bidirectional"))
      (node (ref "U$2") (pin "3") (pinfunction "A2_3") (pintype "bidirectional"))
      (node (ref "U$2") (pin "8") (pinfunction "GND_8") (pintype "bidirectional"))
      (node (ref "U$4") (pin "2") (pinfunction "AIN1_2") (pintype "bidirectional"))
      (node (ref "U$4") (pin "3") (pinfunction "AIN2_3") (pintype "bidirectional"))
      (node (ref "U$4") (pin "4") (pinfunction "AIN3_4") (pintype "bidirectional"))
      (node (ref "U$4") (pin "7") (pinfunction "VEE_7") (pintype "bidirectional"))
      (node (ref "U$6") (pin "P$1") (pinfunction "P$1_P$1") (pintype "bidirectional"))
      (node (ref "U$7") (pin "P$2") (pinfunction "GND_P$2") (pintype "bidirectional"))
    )
    (net (code "13") (name "INPUT_ZERO") (class "Default")
      (node (ref "U$11") (pin "6") (pinfunction "IN_6") (pintype "bidirectional"))
      (node (ref "U$2") (pin "9") (pinfunction "P4_9") (pintype "bidirectional"))
    )
    (net (code "14") (name "N_WE") (class "Default")
      (node (ref "U$2") (pin "7") (pinfunction "P3_7") (pintype "bidirectional"))
    )
    (net (code "15") (name "Net-(CONVERSIONA-VOUT)") (class "Default")
      (node (ref "CONV") (pin "2") (pinfunction "2_2") (pintype "passive"))
      (node (ref "CONVERSION") (pin "5") (pinfunction "VOUT_5") (pintype "output"))
    )
    (net (code "16") (name "Net-(DC-DC_CONVERTER-+VIN(VCC))") (class "Default")
      (node (ref "DC-DC_CONVERTER") (pin "1") (pinfunction "+VIN(VCC)_1") (pintype "power_in"))
      (node (ref "L1") (pin "1") (pinfunction "1_1") (pintype "passive"))
    )
    (net (code "17") (name "Net-(DC-DC_CONVERTER-+VOUT)") (class "Default")
      (node (ref "C18") (pin "1") (pinfunction "1_1") (pintype "passive"))
      (node (ref "DC-DC_CONVERTER") (pin "7") (pinfunction "+VOUT_7") (pintype "output"))
      (node (ref "U$8") (pin "2") (pinfunction "2_2") (pintype "passive"))
    )
    (net (code "18") (name "Net-(DC-DC_CONVERTER--VOUT)") (class "Default")
      (node (ref "C19") (pin "2") (pinfunction "2_2") (pintype "passive"))
      (node (ref "C24") (pin "2") (pinfunction "2_2") (pintype "passive"))
      (node (ref "DC-DC_CONVERTER") (pin "5") (pinfunction "-VOUT_5") (pintype "output"))
      (node (ref "U$9") (pin "2") (pinfunction "2_2") (pintype "passive"))
    )
    (net (code "19") (name "Net-(DC-DC_CONVERTER-ON{slash}OFF)") (class "Default")
      (node (ref "DC-DC_CONVERTER") (pin "4") (pinfunction "ON/OFF_4") (pintype "bidirectional"))
      (node (ref "ON/OFF") (pin "2") (pinfunction "2_2") (pintype "passive"))
    )
    (net (code "20") (name "Net-(I2CA-SCL1)") (class "Default")
      (node (ref "I2C") (pin "3") (pinfunction "SCL1_3") (pintype "bidirectional"))
      (node (ref "R18") (pin "1") (pinfunction "1_1") (pintype "passive"))
      (node (ref "ROHM_I2C") (pin "6") (pinfunction "SCL_6") (pintype "input"))
      (node (ref "U$2") (pin "14") (pinfunction "SCL_14") (pintype "bidirectional"))
      (node (ref "U$4") (pin "5") (pinfunction "SCL_5") (pintype "bidirectional"))
    )
    (net (code "21") (name "Net-(I2CA-SDA1)") (class "Default")
      (node (ref "I2C") (pin "2") (pinfunction "SDA1_2") (pintype "bidirectional"))
      (node (ref "R19") (pin "1") (pinfunction "1_1") (pintype "passive"))
      (node (ref "ROHM_I2C") (pin "5") (pinfunction "SDA_5") (pintype "bidirectional"))
      (node (ref "U$2") (pin "15") (pinfunction "SDA_15") (pintype "bidirectional"))
      (node (ref "U$4") (pin "6") (pinfunction "SDA_6") (pintype "bidirectional"))
    )
    (net (code "22") (name "Net-(ON/OFF-Pad3)") (class "Default")
      (node (ref "ON/OFF") (pin "3") (pinfunction "3_3") (pintype "passive"))
      (node (ref "R2") (pin "2") (pinfunction "2_2") (pintype "passive"))
    )
    (net (code "23") (name "Net-(POWER-PadA)") (class "Default")
      (node (ref "POWER") (pin "A") (pinfunction "A_A") (pintype "passive"))
      (node (ref "R21") (pin "1") (pinfunction "1_1") (pintype "passive"))
    )
    (net (code "24") (name "Net-(POWER1-PadA)") (class "Default")
      (node (ref "POWER1") (pin "A") (pinfunction "A_A") (pintype "passive"))
      (node (ref "R23") (pin "1") (pinfunction "1_1") (pintype "passive"))
    )
    (net (code "25") (name "Net-(R4-S)") (class "Default")
      (node (ref "R4") (pin "2") (pinfunction "S_2") (pintype "passive"))
      (node (ref "R5") (pin "1") (pinfunction "1_1") (pintype "passive"))
      (node (ref "U$3") (pin "6") (pinfunction "-IN_6") (pintype "input"))
    )
    (net (code "26") (name "Net-(R8-Pad1)") (class "Default")
      (node (ref "R8") (pin "1") (pinfunction "1_1") (pintype "passive"))
      (node (ref "STATUS") (pin "A") (pinfunction "A_A") (pintype "passive"))
    )
    (net (code "27") (name "Net-(R11-S)") (class "Default")
      (node (ref "R11") (pin "2") (pinfunction "S_2") (pintype "passive"))
      (node (ref "R3") (pin "1") (pinfunction "1_1") (pintype "passive"))
      (node (ref "U$11") (pin "8") (pinfunction "NO_8") (pintype "bidirectional"))
    )
    (net (code "28") (name "Net-(SERIAL_CLOCKA-DE)") (class "Default")
      (node (ref "DE_CLK") (pin "1") (pinfunction "1_1") (pintype "passive"))
      (node (ref "SERIAL_CLOCK") (pin "10") (pinfunction "DE_10") (pintype "passive"))
    )
    (net (code "29") (name "Net-(SERIAL_CLOCKA-RXD)") (class "Default")
      (node (ref "SCK") (pin "2") (pinfunction "2_2") (pintype "passive"))
      (node (ref "SERIAL_CLOCK") (pin "3") (pinfunction "RXD_3") (pintype "passive"))
    )
    (net (code "30") (name "Net-(SERIAL_DATAA-DE)") (class "Default")
      (node (ref "DE_DATA") (pin "1") (pinfunction "1_1") (pintype "passive"))
      (node (ref "SERIAL_DATA") (pin "10") (pinfunction "DE_10") (pintype "passive"))
    )
    (net (code "31") (name "Net-(SERIAL_DATAA-TXD)") (class "Default")
      (node (ref "SDA") (pin "2") (pinfunction "2_2") (pintype "passive"))
      (node (ref "SERIAL_DATA") (pin "6") (pinfunction "TXD_6") (pintype "passive"))
    )
    (net (code "32") (name "Net-(U$1A-DIN)") (class "Default")
      (node (ref "SDA") (pin "1") (pinfunction "1_1") (pintype "passive"))
      (node (ref "SDA_TP") (pin "TP") (pinfunction "TP_TP") (pintype "input"))
      (node (ref "U$1") (pin "4") (pinfunction "DIN_4") (pintype "bidirectional"))
    )
    (net (code "33") (name "Net-(U$1A-INV)") (class "Default")
      (node (ref "C27") (pin "2") (pinfunction "2_2") (pintype "passive"))
      (node (ref "U$1") (pin "7") (pinfunction "INV_7") (pintype "bidirectional"))
      (node (ref "U$3") (pin "2") (pinfunction "-IN_2") (pintype "input"))
    )
    (net (code "34") (name "Net-(U$1A-RFB)") (class "Default")
      (node (ref "C27") (pin "1") (pinfunction "1_1") (pintype "passive"))
      (node (ref "U$1") (pin "8") (pinfunction "RFB_8") (pintype "bidirectional"))
      (node (ref "U$3") (pin "1") (pinfunction "OUT_1") (pintype "output"))
      (node (ref "U$3") (pin "5") (pinfunction "+IN_5") (pintype "input"))
    )
    (net (code "35") (name "Net-(U$1A-SCLK)") (class "Default")
      (node (ref "SCK") (pin "1") (pinfunction "1_1") (pintype "passive"))
      (node (ref "SCK_TP") (pin "TP") (pinfunction "TP_TP") (pintype "input"))
      (node (ref "U$1") (pin "3") (pinfunction "SCLK_3") (pintype "bidirectional"))
    )
    (net (code "36") (name "Net-(U$1A-VOUT)") (class "Default")
      (node (ref "U$1") (pin "6") (pinfunction "VOUT_6") (pintype "bidirectional"))
      (node (ref "U$3") (pin "3") (pinfunction "+IN_3") (pintype "input"))
    )
    (net (code "37") (name "Net-(U$1A-~{CS})") (class "Default")
      (node (ref "CONV") (pin "1") (pinfunction "1_1") (pintype "passive"))
      (node (ref "CONV_TP") (pin "TP") (pinfunction "TP_TP") (pintype "input"))
      (node (ref "U$1") (pin "2") (pinfunction "~{CS}_2") (pintype "bidirectional"))
    )
    (net (code "38") (name "Net-(U$2-N_INT)") (class "Default")
      (node (ref "R1") (pin "2") (pinfunction "2_2") (pintype "passive"))
      (node (ref "U$2") (pin "13") (pinfunction "N_INT_13") (pintype "bidirectional"))
    )
    (net (code "39") (name "Net-(U$4A-AIN0)") (class "Default")
      (node (ref "R12") (pin "1") (pinfunction "1_1") (pintype "passive"))
      (node (ref "U$4") (pin "1") (pinfunction "AIN0_1") (pintype "bidirectional"))
    )
    (net (code "40") (name "Net-(U$11B-COM)") (class "Default")
      (node (ref "R12") (pin "2") (pinfunction "2_2") (pintype "passive"))
      (node (ref "U$11") (pin "1") (pinfunction "COM_1") (pintype "bidirectional"))
    )
    (net (code "41") (name "REF_") (class "Default")
      (node (ref "C51") (pin "1") (pinfunction "1_1") (pintype "passive"))
      (node (ref "REF") (pin "6") (pinfunction "VOUT_6") (pintype "output"))
      (node (ref "REF_2.5") (pin "1") (pinfunction "1_1") (pintype "passive"))
      (node (ref "U$1") (pin "1") (pinfunction "REF_1") (pintype "bidirectional"))
    )
    (net (code "42") (name "SCL") (class "Default")
      (node (ref "I2C") (pin "6") (pinfunction "SCL2_6") (pintype "bidirectional"))
      (node (ref "R22") (pin "1") (pinfunction "1_1") (pintype "passive"))
      (node (ref "RJ45") (pin "7") (pinfunction "7_7") (pintype "passive"))
    )
    (net (code "43") (name "SDO") (class "Default")
      (node (ref "I2C") (pin "7") (pinfunction "SDA2_7") (pintype "bidirectional"))
      (node (ref "R20") (pin "1") (pinfunction "1_1") (pintype "passive"))
      (node (ref "RJ45") (pin "8") (pinfunction "8_8") (pintype "passive"))
    )
    (net (code "44") (name "STATUS_LED") (class "Default")
      (node (ref "R8") (pin "2") (pinfunction "2_2") (pintype "passive"))
      (node (ref "U$2") (pin "6") (pinfunction "P2_6") (pintype "bidirectional"))
    )
    (net (code "45") (name "VCC") (class "Default")
      (node (ref "C23") (pin "2") (pinfunction "2_2") (pintype "passive"))
      (node (ref "C3") (pin "1") (pinfunction "1_1") (pintype "passive"))
      (node (ref "C6") (pin "1") (pinfunction "1_1") (pintype "passive"))
      (node (ref "C7") (pin "1") (pinfunction "1_1") (pintype "passive"))
      (node (ref "C9") (pin "1") (pinfunction "1_1") (pintype "passive"))
      (node (ref "CONVERSION") (pin "1") (pinfunction "VDD1_1") (pintype "passive"))
      (node (ref "I2C") (pin "8") (pinfunction "VDD2_8") (pintype "passive"))
      (node (ref "L1") (pin "2") (pinfunction "2_2") (pintype "passive"))
      (node (ref "R16") (pin "1") (pinfunction "1_1") (pintype "passive"))
      (node (ref "R2") (pin "1") (pinfunction "1_1") (pintype "passive"))
      (node (ref "R20") (pin "2") (pinfunction "2_2") (pintype "passive"))
      (node (ref "R21") (pin "2") (pinfunction "2_2") (pintype "passive"))
      (node (ref "R22") (pin "2") (pinfunction "2_2") (pintype "passive"))
      (node (ref "R6") (pin "1") (pinfunction "1_1") (pintype "passive"))
      (node (ref "RJ45") (pin "4") (pinfunction "4_4") (pintype "passive"))
      (node (ref "SERIAL_CLOCK") (pin "16") (pinfunction "VDD2_16") (pintype "power_in"))
      (node (ref "SERIAL_DATA") (pin "16") (pinfunction "VDD2_16") (pintype "power_in"))
      (node (ref "VCC") (pin "1") (pinfunction "1_1") (pintype "passive"))
    )
    (net (code "46") (name "V_OUT") (class "Default")
      (node (ref "R11") (pin "1") (pinfunction "E_1") (pintype "passive"))
      (node (ref "R4") (pin "3") (pinfunction "A_3") (pintype "passive"))
      (node (ref "TP1") (pin "TP") (pinfunction "PP_TP") (pintype "input"))
      (node (ref "TP3") (pin "TP") (pinfunction "PP_TP") (pintype "input"))
      (node (ref "U$3") (pin "7") (pinfunction "OUT_7") (pintype "output"))
      (node (ref "U$5") (pin "P$1") (pinfunction "P$1_P$1") (pintype "bidirectional"))
    )
    (net (code "47") (name "unconnected-(ON/OFF-Pad1)") (class "Default")
      (node (ref "ON/OFF") (pin "1") (pinfunction "1_1") (pintype "passive"))
    )
    (net (code "48") (name "unconnected-(R4-E-Pad1)") (class "Default")
      (node (ref "R4") (pin "1") (pinfunction "E_1") (pintype "passive"))
    )
    (net (code "49") (name "unconnected-(R11-A-Pad3)") (class "Default")
      (node (ref "R11") (pin "3") (pinfunction "A_3") (pintype "passive"))
    )
    (net (code "50") (name "unconnected-(REF-DNC-Pad3)") (class "Default")
      (node (ref "REF") (pin "3") (pinfunction "DNC_3") (pintype "no_connect"))
    )
    (net (code "51") (name "unconnected-(REF-DNC_2-Pad5)") (class "Default")
      (node (ref "REF") (pin "5") (pinfunction "DNC_2_5") (pintype "no_connect"))
    )
    (net (code "52") (name "unconnected-(SERIAL_DATAA-RXD-Pad3)") (class "Default")
      (node (ref "SERIAL_DATA") (pin "3") (pinfunction "RXD_3") (pintype "passive"))
    )
    (net (code "53") (name "unconnected-(U$2-P5-Pad10)") (class "Default")
      (node (ref "U$2") (pin "10") (pinfunction "P5_10") (pintype "bidirectional"))
    )
    (net (code "54") (name "unconnected-(U$2-P6-Pad11)") (class "Default")
      (node (ref "U$2") (pin "11") (pinfunction "P6_11") (pintype "bidirectional"))
    )
    (net (code "55") (name "unconnected-(U$2-P7-Pad12)") (class "Default")
      (node (ref "U$2") (pin "12") (pinfunction "P7_12") (pintype "bidirectional"))
    )
  )
)
